# IR_Sensor.net
KiCad netlist of a schematic drawn in EAGLE
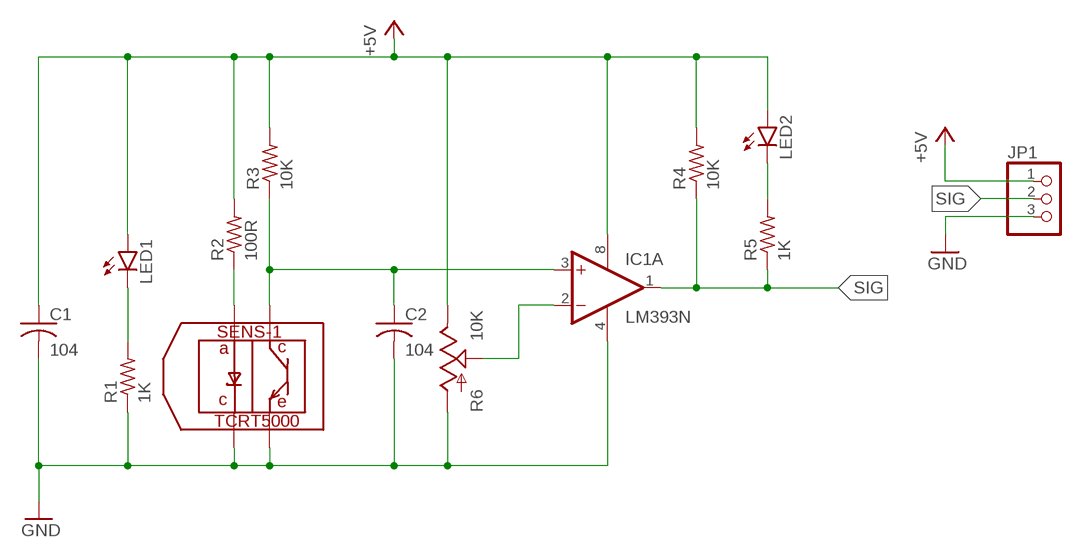
[diagram p0: schematic, sheet 1]

(export (version "E")
  (design (tool "Eeschema 10.0.6"))
  (components
    (comp (ref "C1")
      (value "104")
      (footprint "eagle-import:C050-045X075")
      (libsource (lib "eagle-import") (part "C-US050-045X075"))
    )
    (comp (ref "C2")
      (value "104")
      (footprint "eagle-import:C050-045X075")
      (libsource (lib "eagle-import") (part "C-US050-045X075"))
    )
    (comp (ref "IC1")
      (value "LM393N")
      (footprint "eagle-import:DIL08")
      (libsource (lib "eagle-import") (part "LM393N"))
    )
    (comp (ref "JP1")
      (value "PINHD-1X3")
      (footprint "eagle-import:1X03")
      (libsource (lib "eagle-import") (part "PINHD-1X3"))
    )
    (comp (ref "LED1")
      (value "LED3MM")
      (footprint "eagle-import:LED3MM")
      (libsource (lib "eagle-import") (part "LED3MM"))
    )
    (comp (ref "LED2")
      (value "LED3MM")
      (footprint "eagle-import:LED3MM")
      (libsource (lib "eagle-import") (part "LED3MM"))
    )
    (comp (ref "R1")
      (value "1K")
      (footprint "eagle-import:0207_7")
      (libsource (lib "eagle-import") (part "R-US_0207/7"))
    )
    (comp (ref "R2")
      (value "100R")
      (footprint "eagle-import:0207_7")
      (libsource (lib "eagle-import") (part "R-US_0207/7"))
    )
    (comp (ref "R3")
      (value "10K")
      (footprint "eagle-import:0207_7")
      (libsource (lib "eagle-import") (part "R-US_0207/7"))
    )
    (comp (ref "R4")
      (value "10K")
      (footprint "eagle-import:0207_7")
      (libsource (lib "eagle-import") (part "R-US_0207/7"))
    )
    (comp (ref "R5")
      (value "1K")
      (footprint "eagle-import:0207_7")
      (libsource (lib "eagle-import") (part "R-US_0207/7"))
    )
    (comp (ref "R6")
      (value "10K")
      (footprint "eagle-import:CA6V")
      (libsource (lib "eagle-import") (part "TRIM_US-CA6V"))
    )
    (comp (ref "SENS-1")
      (value "TCRT5000")
      (footprint "eagle-import:5000")
      (libsource (lib "eagle-import") (part "TCRT5000"))
    )
  )
  (nets
    (net (code "1") (name "+5V") (class "Default")
      (node (ref "C1") (pin "1") (pinfunction "1_1") (pintype "passive"))
      (node (ref "IC1") (pin "8") (pinfunction "V+_8") (pintype "power_in"))
      (node (ref "JP1") (pin "1") (pinfunction "1_1") (pintype "passive"))
      (node (ref "LED1") (pin "A") (pinfunction "A_A") (pintype "passive"))
      (node (ref "LED2") (pin "A") (pinfunction "A_A") (pintype "passive"))
      (node (ref "R2") (pin "2") (pinfunction "2_2") (pintype "passive"))
      (node (ref "R3") (pin "2") (pinfunction "2_2") (pintype "passive"))
      (node (ref "R4") (pin "2") (pinfunction "2_2") (pintype "passive"))
      (node (ref "R6") (pin "E") (pinfunction "E_E") (pintype "passive"))
    )
    (net (code "2") (name "GND") (class "Default")
      (node (ref "C1") (pin "2") (pinfunction "2_2") (pintype "passive"))
      (node (ref "C2") (pin "2") (pinfunction "2_2") (pintype "passive"))
      (node (ref "IC1") (pin "4") (pinfunction "V-_4") (pintype "power_in"))
      (node (ref "JP1") (pin "3") (pinfunction "3_3") (pintype "passive"))
      (node (ref "R1") (pin "1") (pinfunction "1_1") (pintype "passive"))
      (node (ref "R6") (pin "A") (pinfunction "A_A") (pintype "passive"))
      (node (ref "SENS-1") (pin "P$2") (pinfunction "P$2_P$2") (pintype "passive"))
      (node (ref "SENS-1") (pin "P$4") (pinfunction "P$4_P$4") (pintype "passive"))
    )
    (net (code "3") (name "Net-(IC1A-+IN)") (class "Default")
      (node (ref "C2") (pin "1") (pinfunction "1_1") (pintype "passive"))
      (node (ref "IC1") (pin "3") (pinfunction "+IN_3") (pintype "input"))
      (node (ref "R3") (pin "1") (pinfunction "1_1") (pintype "passive"))
      (node (ref "SENS-1") (pin "P$1") (pinfunction "P$1_P$1") (pintype "passive"))
    )
    (net (code "4") (name "Net-(IC1A--IN)") (class "Default")
      (node (ref "IC1") (pin "2") (pinfunction "-IN_2") (pintype "input"))
      (node (ref "R6") (pin "S") (pinfunction "S_S") (pintype "passive"))
    )
    (net (code "5") (name "Net-(LED1-C)") (class "Default")
      (node (ref "LED1") (pin "K") (pinfunction "C_K") (pintype "passive"))
      (node (ref "R1") (pin "2") (pinfunction "2_2") (pintype "passive"))
    )
    (net (code "6") (name "Net-(LED2-C)") (class "Default")
      (node (ref "LED2") (pin "K") (pinfunction "C_K") (pintype "passive"))
      (node (ref "R5") (pin "2") (pinfunction "2_2") (pintype "passive"))
    )
    (net (code "7") (name "Net-(R2-Pad1)") (class "Default")
      (node (ref "R2") (pin "1") (pinfunction "1_1") (pintype "passive"))
      (node (ref "SENS-1") (pin "P$3") (pinfunction "P$3_P$3") (pintype "passive"))
    )
    (net (code "8") (name "SIG") (class "Default")
      (node (ref "IC1") (pin "1") (pinfunction "OUT_1") (pintype "output"))
      (node (ref "JP1") (pin "2") (pinfunction "2_2") (pintype "passive"))
      (node (ref "R4") (pin "1") (pinfunction "1_1") (pintype "passive"))
      (node (ref "R5") (pin "1") (pinfunction "1_1") (pintype "passive"))
    )
  )
)
